# S7CAS-PLEIADES-CARTE-MERE_P07_ADC.net
KiCad netlist of a schematic drawn in Altium Designer
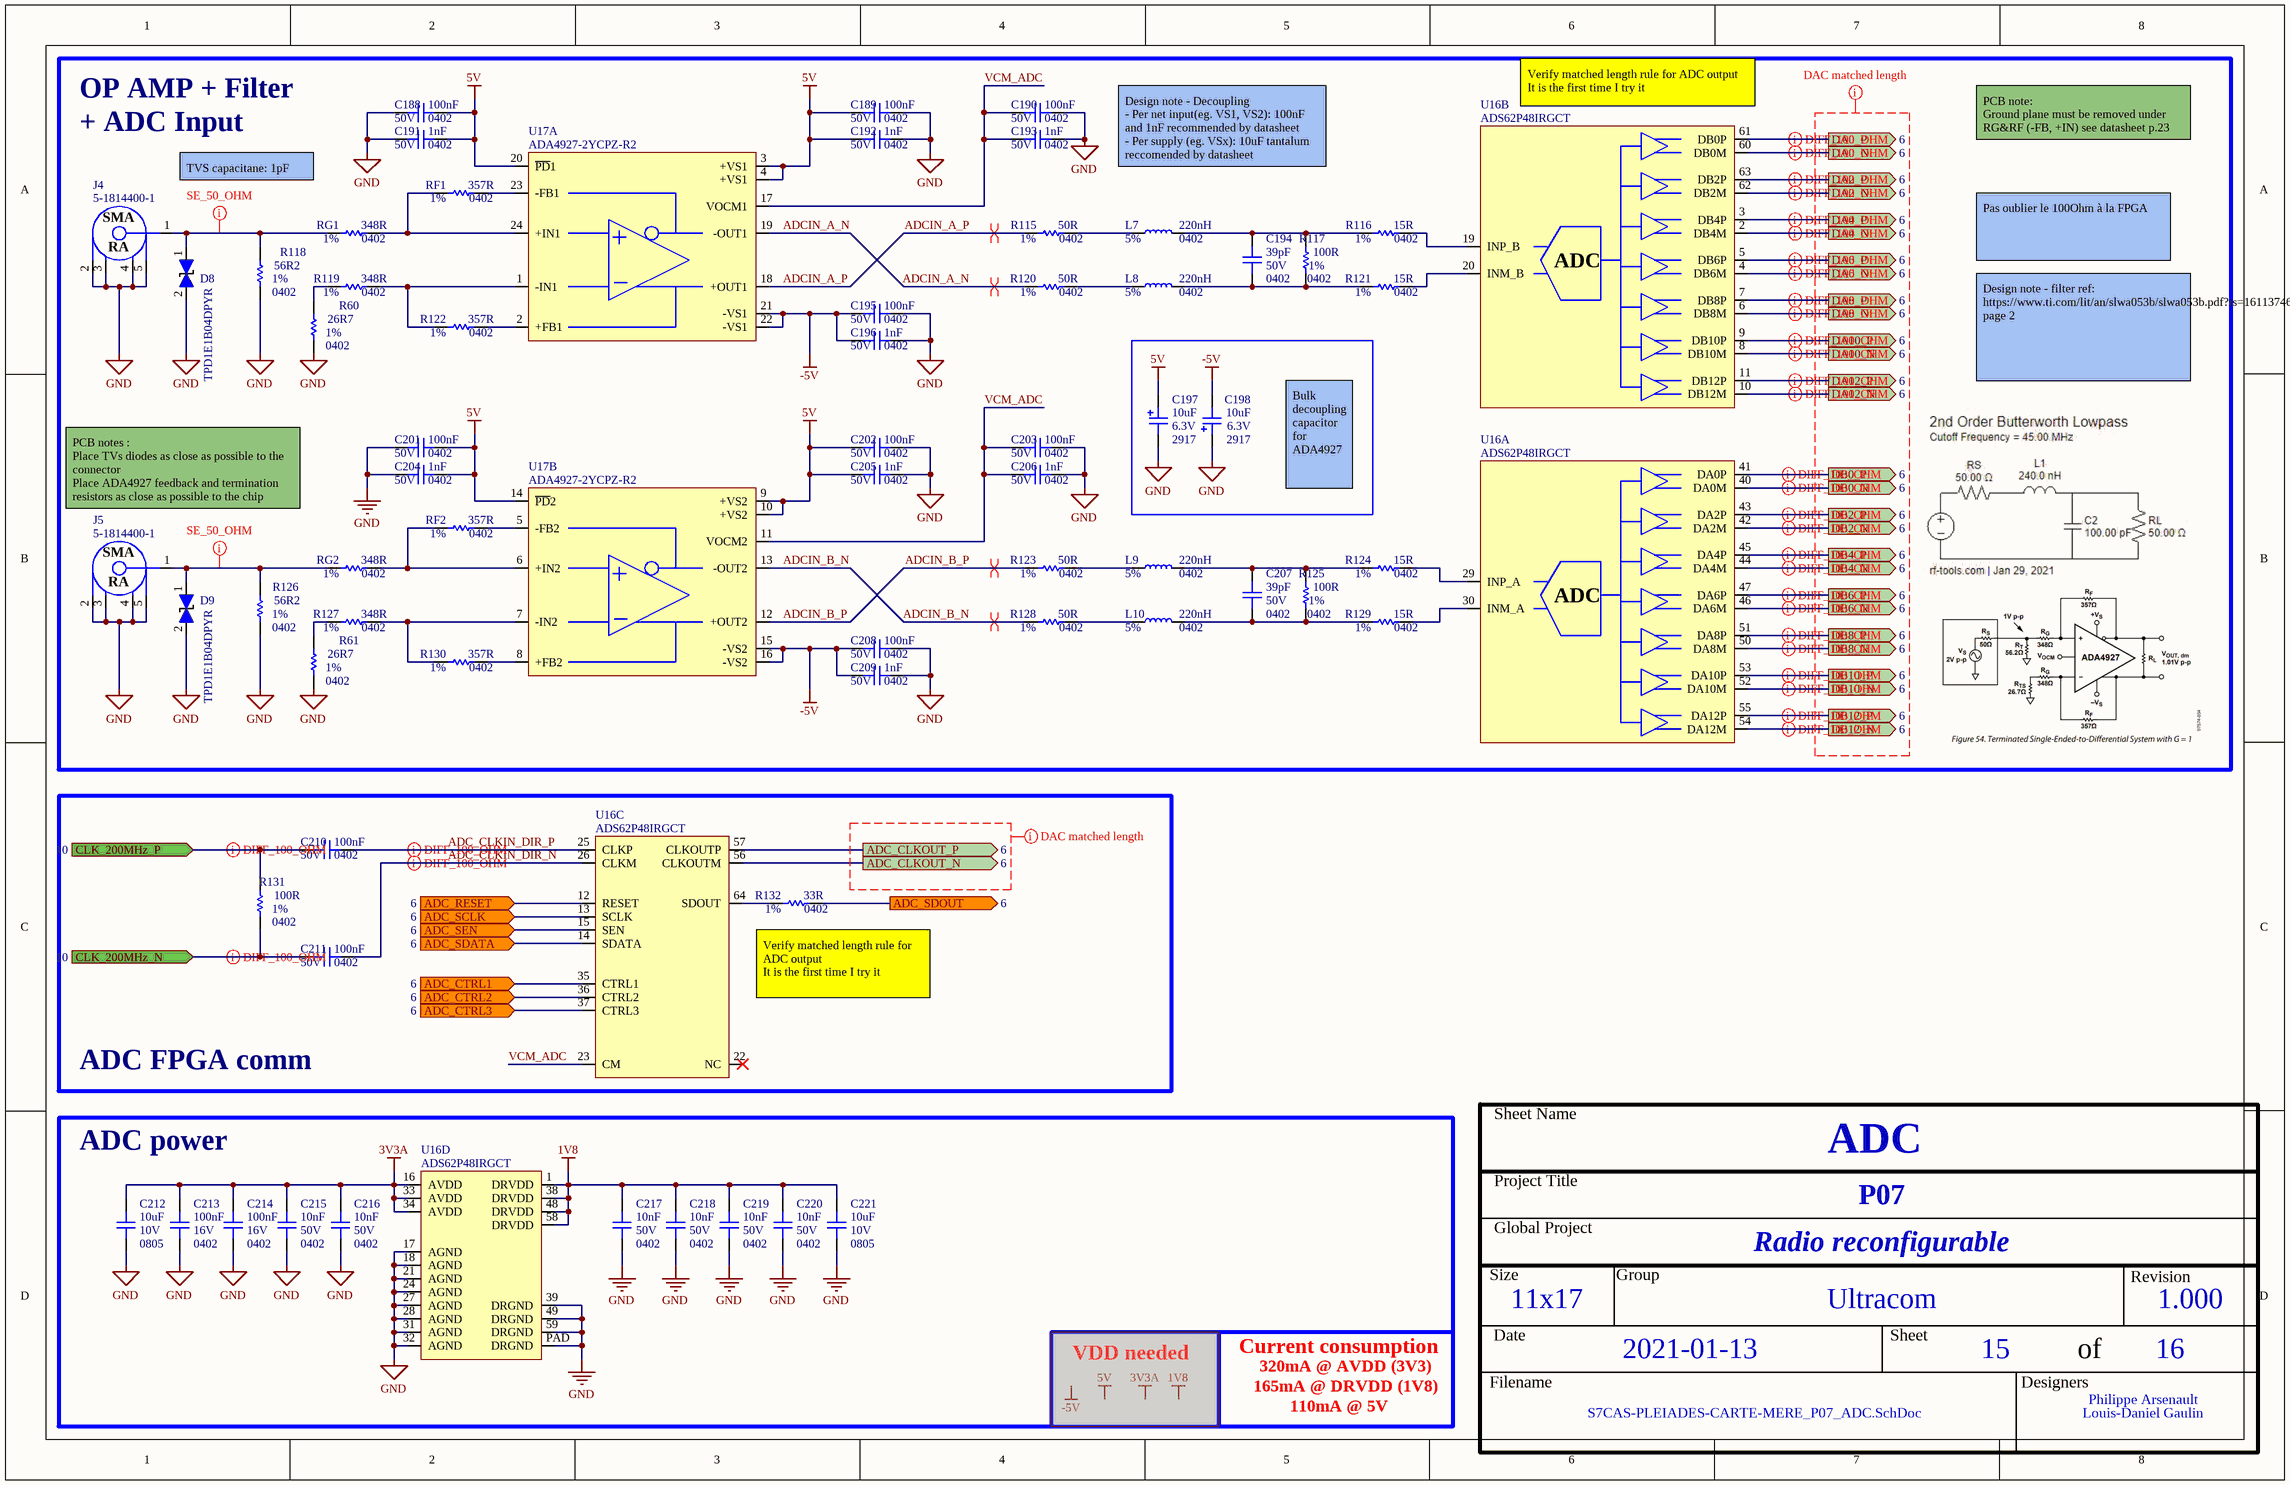
[diagram p0: S7CAS-PLEIADES-CARTE-MERE_P07_ADC.SchDoc]

(export (version "E")
  (design (tool "Eeschema 10.0.6"))
  (components
    (comp (ref "C188")
      (value "100nF")
      (footprint "CAP_0402")
      (description "CAP - 0402")
      (fields
        (field (name "VOLTAGE") "50V")
        (field (name "PACKAGE") "0402")
        (field (name "CREATEDBY") "Jonathan Bouchard")
      )
      (libsource (lib "S7CAS_LIB2021") (part "CAP - 0402"))
    )
    (comp (ref "C189")
      (value "100nF")
      (footprint "CAP_0402")
      (description "CAP - 0402")
      (fields
        (field (name "VOLTAGE") "50V")
        (field (name "PACKAGE") "0402")
        (field (name "CREATEDBY") "Jonathan Bouchard")
      )
      (libsource (lib "S7CAS_LIB2021") (part "CAP - 0402"))
    )
    (comp (ref "C190")
      (value "100nF")
      (footprint "CAP_0402")
      (description "CAP - 0402")
      (fields
        (field (name "VOLTAGE") "50V")
        (field (name "PACKAGE") "0402")
        (field (name "CREATEDBY") "Jonathan Bouchard")
      )
      (libsource (lib "S7CAS_LIB2021") (part "CAP - 0402"))
    )
    (comp (ref "C191")
      (value "1nF")
      (footprint "CAP_0402")
      (description "CAP - 0402")
      (fields
        (field (name "VOLTAGE") "50V")
        (field (name "PACKAGE") "0402")
        (field (name "CREATEDBY") "Jonathan Bouchard")
      )
      (libsource (lib "S7CAS_LIB2021") (part "CAP - 0402"))
    )
    (comp (ref "C192")
      (value "1nF")
      (footprint "CAP_0402")
      (description "CAP - 0402")
      (fields
        (field (name "VOLTAGE") "50V")
        (field (name "PACKAGE") "0402")
        (field (name "CREATEDBY") "Jonathan Bouchard")
      )
      (libsource (lib "S7CAS_LIB2021") (part "CAP - 0402"))
    )
    (comp (ref "C193")
      (value "1nF")
      (footprint "CAP_0402")
      (description "CAP - 0402")
      (fields
        (field (name "VOLTAGE") "50V")
        (field (name "PACKAGE") "0402")
        (field (name "CREATEDBY") "Jonathan Bouchard")
      )
      (libsource (lib "S7CAS_LIB2021") (part "CAP - 0402"))
    )
    (comp (ref "C194")
      (value "39pF")
      (footprint "CAP_0402")
      (description "CAP - 0402")
      (fields
        (field (name "VOLTAGE") "50V")
        (field (name "PACKAGE") "0402")
        (field (name "CREATEDBY") "Jonathan Bouchard")
      )
      (libsource (lib "S7CAS_LIB2021") (part "CAP - 0402"))
    )
    (comp (ref "C195")
      (value "100nF")
      (footprint "CAP_0402")
      (description "CAP - 0402")
      (fields
        (field (name "VOLTAGE") "50V")
        (field (name "PACKAGE") "0402")
        (field (name "CREATEDBY") "Jonathan Bouchard")
      )
      (libsource (lib "S7CAS_LIB2021") (part "CAP - 0402"))
    )
    (comp (ref "C196")
      (value "1nF")
      (footprint "CAP_0402")
      (description "CAP - 0402")
      (fields
        (field (name "VOLTAGE") "50V")
        (field (name "PACKAGE") "0402")
        (field (name "CREATEDBY") "Jonathan Bouchard")
      )
      (libsource (lib "S7CAS_LIB2021") (part "CAP - 0402"))
    )
    (comp (ref "C197")
      (value "10uF")
      (footprint "CAP_TAN_2917(D)")
      (description "CAP - TANTALUM - 2917")
      (fields
        (field (name "VOLTAGE") "6.3V")
        (field (name "PACKAGE") "2917")
        (field (name "Comment") "CAP - TANTALUM - CASE D")
        (field (name "CREATEDBY") "Jonathan Bouchard")
      )
      (libsource (lib "S7CAS_LIB2021") (part "CAP_TANT_2917(D)"))
    )
    (comp (ref "C198")
      (value "10uF")
      (footprint "CAP_TAN_2917(D)")
      (description "CAP - TANTALUM - 2917")
      (fields
        (field (name "VOLTAGE") "6.3V")
        (field (name "PACKAGE") "2917")
        (field (name "Comment") "CAP - TANTALUM - CASE D")
        (field (name "CREATEDBY") "Jonathan Bouchard")
      )
      (libsource (lib "S7CAS_LIB2021") (part "CAP_TANT_2917(D)"))
    )
    (comp (ref "C201")
      (value "100nF")
      (footprint "CAP_0402")
      (description "CAP - 0402")
      (fields
        (field (name "VOLTAGE") "50V")
        (field (name "PACKAGE") "0402")
        (field (name "CREATEDBY") "Jonathan Bouchard")
      )
      (libsource (lib "S7CAS_LIB2021") (part "CAP - 0402"))
    )
    (comp (ref "C202")
      (value "100nF")
      (footprint "CAP_0402")
      (description "CAP - 0402")
      (fields
        (field (name "VOLTAGE") "50V")
        (field (name "PACKAGE") "0402")
        (field (name "CREATEDBY") "Jonathan Bouchard")
      )
      (libsource (lib "S7CAS_LIB2021") (part "CAP - 0402"))
    )
    (comp (ref "C203")
      (value "100nF")
      (footprint "CAP_0402")
      (description "CAP - 0402")
      (fields
        (field (name "VOLTAGE") "50V")
        (field (name "PACKAGE") "0402")
        (field (name "CREATEDBY") "Jonathan Bouchard")
      )
      (libsource (lib "S7CAS_LIB2021") (part "CAP - 0402"))
    )
    (comp (ref "C204")
      (value "1nF")
      (footprint "CAP_0402")
      (description "CAP - 0402")
      (fields
        (field (name "VOLTAGE") "50V")
        (field (name "PACKAGE") "0402")
        (field (name "CREATEDBY") "Jonathan Bouchard")
      )
      (libsource (lib "S7CAS_LIB2021") (part "CAP - 0402"))
    )
    (comp (ref "C205")
      (value "1nF")
      (footprint "CAP_0402")
      (description "CAP - 0402")
      (fields
        (field (name "VOLTAGE") "50V")
        (field (name "PACKAGE") "0402")
        (field (name "CREATEDBY") "Jonathan Bouchard")
      )
      (libsource (lib "S7CAS_LIB2021") (part "CAP - 0402"))
    )
    (comp (ref "C206")
      (value "1nF")
      (footprint "CAP_0402")
      (description "CAP - 0402")
      (fields
        (field (name "VOLTAGE") "50V")
        (field (name "PACKAGE") "0402")
        (field (name "CREATEDBY") "Jonathan Bouchard")
      )
      (libsource (lib "S7CAS_LIB2021") (part "CAP - 0402"))
    )
    (comp (ref "C207")
      (value "39pF")
      (footprint "CAP_0402")
      (description "CAP - 0402")
      (fields
        (field (name "VOLTAGE") "50V")
        (field (name "PACKAGE") "0402")
        (field (name "CREATEDBY") "Jonathan Bouchard")
      )
      (libsource (lib "S7CAS_LIB2021") (part "CAP - 0402"))
    )
    (comp (ref "C208")
      (value "100nF")
      (footprint "CAP_0402")
      (description "CAP - 0402")
      (fields
        (field (name "VOLTAGE") "50V")
        (field (name "PACKAGE") "0402")
        (field (name "CREATEDBY") "Jonathan Bouchard")
      )
      (libsource (lib "S7CAS_LIB2021") (part "CAP - 0402"))
    )
    (comp (ref "C209")
      (value "1nF")
      (footprint "CAP_0402")
      (description "CAP - 0402")
      (fields
        (field (name "VOLTAGE") "50V")
        (field (name "PACKAGE") "0402")
        (field (name "CREATEDBY") "Jonathan Bouchard")
      )
      (libsource (lib "S7CAS_LIB2021") (part "CAP - 0402"))
    )
    (comp (ref "C210")
      (value "100nF")
      (footprint "CAP_0402")
      (description "CAP - 0402")
      (fields
        (field (name "VOLTAGE") "50V")
        (field (name "PACKAGE") "0402")
        (field (name "CREATEDBY") "Jonathan Bouchard")
      )
      (libsource (lib "S7CAS_LIB2021") (part "CAP - 0402"))
    )
    (comp (ref "C211")
      (value "100nF")
      (footprint "CAP_0402")
      (description "CAP - 0402")
      (fields
        (field (name "VOLTAGE") "50V")
        (field (name "PACKAGE") "0402")
        (field (name "CREATEDBY") "Jonathan Bouchard")
      )
      (libsource (lib "S7CAS_LIB2021") (part "CAP - 0402"))
    )
    (comp (ref "C212")
      (value "10uF")
      (footprint "CAP_0805")
      (description "CAP - 0805")
      (fields
        (field (name "MFG") "CL21B106KPQNNNE")
        (field (name "VOLTAGE") "10V")
        (field (name "PACKAGE") "0805")
        (field (name "CREATEDBY") "Jonathan Bouchard")
      )
      (libsource (lib "S7CAS_LIB2021") (part "CAP - 0805"))
    )
    (comp (ref "C213")
      (value "100nF")
      (footprint "CAP_0402")
      (description "CAP - 0402")
      (fields
        (field (name "MFG PART NUMBER") "CL05B104KO5NNNC")
        (field (name "VOLTAGE") "16V")
        (field (name "PACKAGE") "0402")
        (field (name "CREATEDBY") "Jonathan Bouchard")
      )
      (libsource (lib "S7CAS_LIB2021") (part "CAP - 0402"))
    )
    (comp (ref "C214")
      (value "100nF")
      (footprint "CAP_0402")
      (description "CAP - 0402")
      (fields
        (field (name "MFG PART NUMBER") "CL05B104KO5NNNC")
        (field (name "VOLTAGE") "16V")
        (field (name "PACKAGE") "0402")
        (field (name "CREATEDBY") "Jonathan Bouchard")
      )
      (libsource (lib "S7CAS_LIB2021") (part "CAP - 0402"))
    )
    (comp (ref "C215")
      (value "10nF")
      (footprint "CAP_0402")
      (description "CAP - 0402")
      (fields
        (field (name "MFG PART NUMBER") "CL05B103KB5NNNC")
        (field (name "VOLTAGE") "50V")
        (field (name "PACKAGE") "0402")
        (field (name "CREATEDBY") "Jonathan Bouchard")
      )
      (libsource (lib "S7CAS_LIB2021") (part "CAP - 0402"))
    )
    (comp (ref "C216")
      (value "10nF")
      (footprint "CAP_0402")
      (description "CAP - 0402")
      (fields
        (field (name "MFG PART NUMBER") "CL05B103KB5NNNC")
        (field (name "VOLTAGE") "50V")
        (field (name "PACKAGE") "0402")
        (field (name "CREATEDBY") "Jonathan Bouchard")
      )
      (libsource (lib "S7CAS_LIB2021") (part "CAP - 0402"))
    )
    (comp (ref "C217")
      (value "10nF")
      (footprint "CAP_0402")
      (description "CAP - 0402")
      (fields
        (field (name "MFG PART NUMBER") "CL05B103KB5NNNC")
        (field (name "VOLTAGE") "50V")
        (field (name "PACKAGE") "0402")
        (field (name "CREATEDBY") "Jonathan Bouchard")
      )
      (libsource (lib "S7CAS_LIB2021") (part "CAP - 0402"))
    )
    (comp (ref "C218")
      (value "10nF")
      (footprint "CAP_0402")
      (description "CAP - 0402")
      (fields
        (field (name "MFG PART NUMBER") "CL05B103KB5NNNC")
        (field (name "VOLTAGE") "50V")
        (field (name "PACKAGE") "0402")
        (field (name "CREATEDBY") "Jonathan Bouchard")
      )
      (libsource (lib "S7CAS_LIB2021") (part "CAP - 0402"))
    )
    (comp (ref "C219")
      (value "10nF")
      (footprint "CAP_0402")
      (description "CAP - 0402")
      (fields
        (field (name "MFG PART NUMBER") "CL05B103KB5NNNC")
        (field (name "VOLTAGE") "50V")
        (field (name "PACKAGE") "0402")
        (field (name "CREATEDBY") "Jonathan Bouchard")
      )
      (libsource (lib "S7CAS_LIB2021") (part "CAP - 0402"))
    )
    (comp (ref "C220")
      (value "10nF")
      (footprint "CAP_0402")
      (description "CAP - 0402")
      (fields
        (field (name "MFG PART NUMBER") "CL05B103KB5NNNC")
        (field (name "VOLTAGE") "50V")
        (field (name "PACKAGE") "0402")
        (field (name "CREATEDBY") "Jonathan Bouchard")
      )
      (libsource (lib "S7CAS_LIB2021") (part "CAP - 0402"))
    )
    (comp (ref "C221")
      (value "10uF")
      (footprint "CAP_0805")
      (description "CAP - 0805")
      (fields
        (field (name "MFG") "CL21B106KPQNNNE")
        (field (name "VOLTAGE") "10V")
        (field (name "PACKAGE") "0805")
        (field (name "CREATEDBY") "Jonathan Bouchard")
      )
      (libsource (lib "S7CAS_LIB2021") (part "CAP - 0805"))
    )
    (comp (ref "D8")
      (value "TPD1E1B04DPYR")
      (footprint "TVS_DATA_TPD1E1B04DPYR")
      (description "TVS - TVS DIODE 3.6V 8.5V - 0402")
      (fields
        (field (name "CREATEDBY/DATE") "Keven Deslandes - 2018/10/19")
        (field (name "VERIFIEDBY") "Caroline Paulin - 28 janv 2019")
      )
      (libsource (lib "S7CAS_LIB2021") (part "TVS_DATA_TPD1E1B04DPYR"))
    )
    (comp (ref "D9")
      (value "TPD1E1B04DPYR")
      (footprint "TVS_DATA_TPD1E1B04DPYR")
      (description "TVS - TVS DIODE 3.6V 8.5V - 0402")
      (fields
        (field (name "CREATEDBY/DATE") "Keven Deslandes - 2018/10/19")
        (field (name "VERIFIEDBY") "Caroline Paulin - 28 janv 2019")
      )
      (libsource (lib "S7CAS_LIB2021") (part "TVS_DATA_TPD1E1B04DPYR"))
    )
    (comp (ref "J4")
      (value "5-1814400-1")
      (footprint "CONN_SMA_5-1814400-1")
      (description "CONN -  SMA JACK R/A 50 OHM - TH")
      (fields
        (field (name "MFG") "TE Connectivity AMP Connectors")
        (field (name "CREATEDBY") "Jonathan Bouchard")
      )
      (libsource (lib "S7CAS_LIB2021") (part "CONN_SMA_5-1814400-1"))
    )
    (comp (ref "J5")
      (value "5-1814400-1")
      (footprint "CONN_SMA_5-1814400-1")
      (description "CONN -  SMA JACK R/A 50 OHM - TH")
      (fields
        (field (name "MFG") "TE Connectivity AMP Connectors")
        (field (name "CREATEDBY") "Jonathan Bouchard")
      )
      (libsource (lib "S7CAS_LIB2021") (part "CONN_SMA_5-1814400-1"))
    )
    (comp (ref "L7")
      (value "220nH")
      (footprint "IND_0402")
      (description "IND_0402")
      (fields
        (field (name "PRECISION") "5%")
        (field (name "PACKAGE") "0402")
        (field (name "CREATEDBY") "Jonathan Bouchard")
      )
      (libsource (lib "S7CAS_P07") (part "IND_0402"))
    )
    (comp (ref "L8")
      (value "220nH")
      (footprint "IND_0402")
      (description "IND_0402")
      (fields
        (field (name "PRECISION") "5%")
        (field (name "PACKAGE") "0402")
        (field (name "CREATEDBY") "Jonathan Bouchard")
      )
      (libsource (lib "S7CAS_P07") (part "IND_0402"))
    )
    (comp (ref "L9")
      (value "220nH")
      (footprint "IND_0402")
      (description "IND_0402")
      (fields
        (field (name "PRECISION") "5%")
        (field (name "PACKAGE") "0402")
        (field (name "CREATEDBY") "Jonathan Bouchard")
      )
      (libsource (lib "S7CAS_P07") (part "IND_0402"))
    )
    (comp (ref "L10")
      (value "220nH")
      (footprint "IND_0402")
      (description "IND_0402")
      (fields
        (field (name "PRECISION") "5%")
        (field (name "PACKAGE") "0402")
        (field (name "CREATEDBY") "Jonathan Bouchard")
      )
      (libsource (lib "S7CAS_P07") (part "IND_0402"))
    )
    (comp (ref "R60")
      (value "26R7")
      (footprint "RES_0402")
      (description "RES - 0402")
      (fields
        (field (name "VOLTAGE") "50V")
        (field (name "POWER") "1/16W")
        (field (name "PACKAGE") "0402")
        (field (name "PRECISION") "1%")
        (field (name "CREATEDBY") "Jonathan Bouchard")
      )
      (libsource (lib "S7CAS_LIB2021") (part "RES - 0402"))
    )
    (comp (ref "R61")
      (value "26R7")
      (footprint "RES_0402")
      (description "RES - 0402")
      (fields
        (field (name "VOLTAGE") "50V")
        (field (name "POWER") "1/16W")
        (field (name "PACKAGE") "0402")
        (field (name "PRECISION") "1%")
        (field (name "CREATEDBY") "Jonathan Bouchard")
      )
      (libsource (lib "S7CAS_LIB2021") (part "RES - 0402"))
    )
    (comp (ref "R115")
      (value "50R")
      (footprint "RES_0402")
      (description "RES - 0402")
      (fields
        (field (name "VOLTAGE") "50V")
        (field (name "POWER") "1/16W")
        (field (name "PACKAGE") "0402")
        (field (name "PRECISION") "1%")
        (field (name "CREATEDBY") "Jonathan Bouchard")
      )
      (libsource (lib "S7CAS_LIB2021") (part "RES - 0402"))
    )
    (comp (ref "R116")
      (value "15R")
      (footprint "RES_0402")
      (description "RES - 0402")
      (fields
        (field (name "VOLTAGE") "50V")
        (field (name "POWER") "1/16W")
        (field (name "PACKAGE") "0402")
        (field (name "PRECISION") "1%")
        (field (name "CREATEDBY") "Jonathan Bouchard")
      )
      (libsource (lib "S7CAS_LIB2021") (part "RES - 0402"))
    )
    (comp (ref "R117")
      (value "100R")
      (footprint "RES_0402")
      (description "RES - 0402")
      (fields
        (field (name "VOLTAGE") "50V")
        (field (name "POWER") "1/16W")
        (field (name "PACKAGE") "0402")
        (field (name "PRECISION") "1%")
        (field (name "CREATEDBY") "Jonathan Bouchard")
      )
      (libsource (lib "S7CAS_LIB2021") (part "RES - 0402"))
    )
    (comp (ref "R118")
      (value "56R2")
      (footprint "RES_0402")
      (description "RES - 0402")
      (fields
        (field (name "VOLTAGE") "50V")
        (field (name "POWER") "1/16W")
        (field (name "PACKAGE") "0402")
        (field (name "PRECISION") "1%")
        (field (name "CREATEDBY") "Jonathan Bouchard")
      )
      (libsource (lib "S7CAS_LIB2021") (part "RES - 0402"))
    )
    (comp (ref "R119")
      (value "348R")
      (footprint "RES_0402")
      (description "RES - 0402")
      (fields
        (field (name "VOLTAGE") "50V")
        (field (name "POWER") "1/16W")
        (field (name "PACKAGE") "0402")
        (field (name "PRECISION") "1%")
        (field (name "CREATEDBY") "Jonathan Bouchard")
      )
      (libsource (lib "S7CAS_LIB2021") (part "RES - 0402"))
    )
    (comp (ref "R120")
      (value "50R")
      (footprint "RES_0402")
      (description "RES - 0402")
      (fields
        (field (name "VOLTAGE") "50V")
        (field (name "POWER") "1/16W")
        (field (name "PACKAGE") "0402")
        (field (name "PRECISION") "1%")
        (field (name "CREATEDBY") "Jonathan Bouchard")
      )
      (libsource (lib "S7CAS_LIB2021") (part "RES - 0402"))
    )
    (comp (ref "R121")
      (value "15R")
      (footprint "RES_0402")
      (description "RES - 0402")
      (fields
        (field (name "VOLTAGE") "50V")
        (field (name "POWER") "1/16W")
        (field (name "PACKAGE") "0402")
        (field (name "PRECISION") "1%")
        (field (name "CREATEDBY") "Jonathan Bouchard")
      )
      (libsource (lib "S7CAS_LIB2021") (part "RES - 0402"))
    )
    (comp (ref "R122")
      (value "357R")
      (footprint "RES_0402")
      (description "RES - 0402")
      (fields
        (field (name "VOLTAGE") "50V")
        (field (name "POWER") "1/16W")
        (field (name "PACKAGE") "0402")
        (field (name "PRECISION") "1%")
        (field (name "CREATEDBY") "Jonathan Bouchard")
      )
      (libsource (lib "S7CAS_LIB2021") (part "RES - 0402"))
    )
    (comp (ref "R123")
      (value "50R")
      (footprint "RES_0402")
      (description "RES - 0402")
      (fields
        (field (name "VOLTAGE") "50V")
        (field (name "POWER") "1/16W")
        (field (name "PACKAGE") "0402")
        (field (name "PRECISION") "1%")
        (field (name "CREATEDBY") "Jonathan Bouchard")
      )
      (libsource (lib "S7CAS_LIB2021") (part "RES - 0402"))
    )
    (comp (ref "R124")
      (value "15R")
      (footprint "RES_0402")
      (description "RES - 0402")
      (fields
        (field (name "VOLTAGE") "50V")
        (field (name "POWER") "1/16W")
        (field (name "PACKAGE") "0402")
        (field (name "PRECISION") "1%")
        (field (name "CREATEDBY") "Jonathan Bouchard")
      )
      (libsource (lib "S7CAS_LIB2021") (part "RES - 0402"))
    )
    (comp (ref "R125")
      (value "100R")
      (footprint "RES_0402")
      (description "RES - 0402")
      (fields
        (field (name "VOLTAGE") "50V")
        (field (name "POWER") "1/16W")
        (field (name "PACKAGE") "0402")
        (field (name "PRECISION") "1%")
        (field (name "CREATEDBY") "Jonathan Bouchard")
      )
      (libsource (lib "S7CAS_LIB2021") (part "RES - 0402"))
    )
    (comp (ref "R126")
      (value "56R2")
      (footprint "RES_0402")
      (description "RES - 0402")
      (fields
        (field (name "VOLTAGE") "50V")
        (field (name "POWER") "1/16W")
        (field (name "PACKAGE") "0402")
        (field (name "PRECISION") "1%")
        (field (name "CREATEDBY") "Jonathan Bouchard")
      )
      (libsource (lib "S7CAS_LIB2021") (part "RES - 0402"))
    )
    (comp (ref "R127")
      (value "348R")
      (footprint "RES_0402")
      (description "RES - 0402")
      (fields
        (field (name "VOLTAGE") "50V")
        (field (name "POWER") "1/16W")
        (field (name "PACKAGE") "0402")
        (field (name "PRECISION") "1%")
        (field (name "CREATEDBY") "Jonathan Bouchard")
      )
      (libsource (lib "S7CAS_LIB2021") (part "RES - 0402"))
    )
    (comp (ref "R128")
      (value "50R")
      (footprint "RES_0402")
      (description "RES - 0402")
      (fields
        (field (name "VOLTAGE") "50V")
        (field (name "POWER") "1/16W")
        (field (name "PACKAGE") "0402")
        (field (name "PRECISION") "1%")
        (field (name "CREATEDBY") "Jonathan Bouchard")
      )
      (libsource (lib "S7CAS_LIB2021") (part "RES - 0402"))
    )
    (comp (ref "R129")
      (value "15R")
      (footprint "RES_0402")
      (description "RES - 0402")
      (fields
        (field (name "VOLTAGE") "50V")
        (field (name "POWER") "1/16W")
        (field (name "PACKAGE") "0402")
        (field (name "PRECISION") "1%")
        (field (name "CREATEDBY") "Jonathan Bouchard")
      )
      (libsource (lib "S7CAS_LIB2021") (part "RES - 0402"))
    )
    (comp (ref "R130")
      (value "357R")
      (footprint "RES_0402")
      (description "RES - 0402")
      (fields
        (field (name "VOLTAGE") "50V")
        (field (name "POWER") "1/16W")
        (field (name "PACKAGE") "0402")
        (field (name "PRECISION") "1%")
        (field (name "CREATEDBY") "Jonathan Bouchard")
      )
      (libsource (lib "S7CAS_LIB2021") (part "RES - 0402"))
    )
    (comp (ref "R131")
      (value "100R")
      (footprint "RES_0402")
      (description "RES - 0402")
      (fields
        (field (name "VOLTAGE") "50V")
        (field (name "POWER") "1/16W")
        (field (name "PACKAGE") "0402")
        (field (name "PRECISION") "1%")
        (field (name "CREATEDBY") "Jonathan Bouchard")
      )
      (libsource (lib "S7CAS_LIB2021") (part "RES - 0402"))
    )
    (comp (ref "R132")
      (value "33R")
      (footprint "RES_0402")
      (description "RES - 0402")
      (fields
        (field (name "VOLTAGE") "50V")
        (field (name "POWER") "1/16W")
        (field (name "PACKAGE") "0402")
        (field (name "PRECISION") "1%")
        (field (name "CREATEDBY") "Jonathan Bouchard")
      )
      (libsource (lib "S7CAS_LIB2021") (part "RES - 0402"))
    )
    (comp (ref "RF1")
      (value "357R")
      (footprint "RES_0402")
      (description "RES - 0402")
      (fields
        (field (name "VOLTAGE") "50V")
        (field (name "POWER") "1/16W")
        (field (name "PACKAGE") "0402")
        (field (name "PRECISION") "1%")
        (field (name "CREATEDBY") "Jonathan Bouchard")
      )
      (libsource (lib "S7CAS_LIB2021") (part "RES - 0402"))
    )
    (comp (ref "RF2")
      (value "357R")
      (footprint "RES_0402")
      (description "RES - 0402")
      (fields
        (field (name "VOLTAGE") "50V")
        (field (name "POWER") "1/16W")
        (field (name "PACKAGE") "0402")
        (field (name "PRECISION") "1%")
        (field (name "CREATEDBY") "Jonathan Bouchard")
      )
      (libsource (lib "S7CAS_LIB2021") (part "RES - 0402"))
    )
    (comp (ref "RG1")
      (value "348R")
      (footprint "RES_0402")
      (description "RES - 0402")
      (fields
        (field (name "VOLTAGE") "50V")
        (field (name "POWER") "1/16W")
        (field (name "PACKAGE") "0402")
        (field (name "PRECISION") "1%")
        (field (name "CREATEDBY") "Jonathan Bouchard")
      )
      (libsource (lib "S7CAS_LIB2021") (part "RES - 0402"))
    )
    (comp (ref "RG2")
      (value "348R")
      (footprint "RES_0402")
      (description "RES - 0402")
      (fields
        (field (name "VOLTAGE") "50V")
        (field (name "POWER") "1/16W")
        (field (name "PACKAGE") "0402")
        (field (name "PRECISION") "1%")
        (field (name "CREATEDBY") "Jonathan Bouchard")
      )
      (libsource (lib "S7CAS_LIB2021") (part "RES - 0402"))
    )
    (comp (ref "U16")
      (value "ADS62P48IRGCT")
      (footprint "ADC_ADS62P48IRGCT")
      (description "ADC - 14 BIT 210MSPS SUAL - VQFN-64")
      (fields
        (field (name "VOLTAGE") "3.15 V ~ 3.6 V / 1.7 V ~ 1.9 V")
        (field (name "MFG") "Texas Instruments")
        (field (name "CREATEDBY") "Jonathan Bouchard")
      )
      (libsource (lib "S7CAS_LIB2021") (part "ADC_ADS62P48IRGCT"))
    )
    (comp (ref "U17")
      (value "ADA4927-2YCPZ-R2")
      (footprint "OPAMP_ADA4927-2YCPZ-R2")
      (description "OPAMP - CFA 2.3GHZ - QFN-24")
      (fields
        (field (name "VOLTAGE") "4.5 V ~ 11 V, ±2.25 V ~ 5.5 V")
        (field (name "MFG") "Analog Devices")
        (field (name "CREATEDBY") "Jonathan Bouchard")
      )
      (libsource (lib "S7CAS_LIB2021") (part "OPAMP_ADA4927-2YCPZ-R2"))
    )
  )
  (nets
    (net (code "1") (name "-5V") (class "Default")
      (node (ref "C195") (pin "2") (pinfunction "2_2") (pintype "passive"))
      (node (ref "C196") (pin "2") (pinfunction "2_2") (pintype "passive"))
      (node (ref "C198") (pin "2") (pinfunction "2_2") (pintype "passive"))
      (node (ref "C208") (pin "2") (pinfunction "2_2") (pintype "passive"))
      (node (ref "C209") (pin "2") (pinfunction "2_2") (pintype "passive"))
      (node (ref "U17") (pin "15") (pinfunction "-VS2_15") (pintype "passive"))
      (node (ref "U17") (pin "16") (pinfunction "-VS2_16") (pintype "passive"))
      (node (ref "U17") (pin "21") (pinfunction "-VS1_21") (pintype "passive"))
      (node (ref "U17") (pin "22") (pinfunction "-VS1_22") (pintype "passive"))
    )
    (net (code "2") (name "/ADCIN_A_N") (class "Default")
      (node (ref "R120") (pin "2") (pinfunction "2_2") (pintype "passive"))
      (node (ref "U17") (pin "19") (pinfunction "-OUT1_19") (pintype "passive"))
    )
    (net (code "3") (name "/ADCIN_A_P") (class "Default")
      (node (ref "R115") (pin "2") (pinfunction "2_2") (pintype "passive"))
      (node (ref "U17") (pin "18") (pinfunction "+OUT1_18") (pintype "passive"))
    )
    (net (code "4") (name "/ADCIN_B_N") (class "Default")
      (node (ref "R128") (pin "2") (pinfunction "2_2") (pintype "passive"))
      (node (ref "U17") (pin "13") (pinfunction "-OUT2_13") (pintype "passive"))
    )
    (net (code "5") (name "/ADCIN_B_P") (class "Default")
      (node (ref "R123") (pin "2") (pinfunction "2_2") (pintype "passive"))
      (node (ref "U17") (pin "12") (pinfunction "+OUT2_12") (pintype "passive"))
    )
    (net (code "6") (name "/ADC_CLKIN_DIR_N") (class "Default")
      (node (ref "C211") (pin "1") (pinfunction "1_1") (pintype "passive"))
      (node (ref "U16") (pin "26") (pinfunction "CLKM_26") (pintype "passive"))
    )
    (net (code "7") (name "/ADC_CLKIN_DIR_P") (class "Default")
      (node (ref "C210") (pin "1") (pinfunction "1_1") (pintype "passive"))
      (node (ref "U16") (pin "25") (pinfunction "CLKP_25") (pintype "passive"))
    )
    (net (code "8") (name "/ADC_CLKOUT_N") (class "Default")
      (node (ref "U16") (pin "56") (pinfunction "CLKOUTM_56") (pintype "passive"))
    )
    (net (code "9") (name "/ADC_CLKOUT_P") (class "Default")
      (node (ref "U16") (pin "57") (pinfunction "CLKOUTP_57") (pintype "passive"))
    )
    (net (code "10") (name "/ADC_CTRL1") (class "Default")
      (node (ref "U16") (pin "35") (pinfunction "CTRL1_35") (pintype "passive"))
    )
    (net (code "11") (name "/ADC_CTRL2") (class "Default")
      (node (ref "U16") (pin "36") (pinfunction "CTRL2_36") (pintype "passive"))
    )
    (net (code "12") (name "/ADC_CTRL3") (class "Default")
      (node (ref "U16") (pin "37") (pinfunction "CTRL3_37") (pintype "passive"))
    )
    (net (code "13") (name "/ADC_RESET") (class "Default")
      (node (ref "U16") (pin "12") (pinfunction "RESET_12") (pintype "passive"))
    )
    (net (code "14") (name "/ADC_SCLK") (class "Default")
      (node (ref "U16") (pin "13") (pinfunction "SCLK_13") (pintype "passive"))
    )
    (net (code "15") (name "/ADC_SDATA") (class "Default")
      (node (ref "U16") (pin "14") (pinfunction "SDATA_14") (pintype "passive"))
    )
    (net (code "16") (name "/ADC_SDOUT") (class "Default")
      (node (ref "R132") (pin "1") (pinfunction "1_1") (pintype "passive"))
    )
    (net (code "17") (name "/ADC_SEN") (class "Default")
      (node (ref "U16") (pin "15") (pinfunction "SEN_15") (pintype "passive"))
    )
    (net (code "18") (name "/CLK_200MHz_N") (class "Default")
      (node (ref "C211") (pin "2") (pinfunction "2_2") (pintype "passive"))
      (node (ref "R131") (pin "1") (pinfunction "1_1") (pintype "passive"))
    )
    (net (code "19") (name "/CLK_200MHz_P") (class "Default")
      (node (ref "C210") (pin "2") (pinfunction "2_2") (pintype "passive"))
      (node (ref "R131") (pin "2") (pinfunction "2_2") (pintype "passive"))
    )
    (net (code "20") (name "/DA0_N") (class "Default")
      (node (ref "U16") (pin "60") (pinfunction "DB0M_60") (pintype "passive"))
    )
    (net (code "21") (name "/DA0_P") (class "Default")
      (node (ref "U16") (pin "61") (pinfunction "DB0P_61") (pintype "passive"))
    )
    (net (code "22") (name "/DA2_N") (class "Default")
      (node (ref "U16") (pin "62") (pinfunction "DB2M_62") (pintype "passive"))
    )
    (net (code "23") (name "/DA2_P") (class "Default")
      (node (ref "U16") (pin "63") (pinfunction "DB2P_63") (pintype "passive"))
    )
    (net (code "24") (name "/DA4_N") (class "Default")
      (node (ref "U16") (pin "2") (pinfunction "DB4M_2") (pintype "passive"))
    )
    (net (code "25") (name "/DA4_P") (class "Default")
      (node (ref "U16") (pin "3") (pinfunction "DB4P_3") (pintype "passive"))
    )
    (net (code "26") (name "/DA6_N") (class "Default")
      (node (ref "U16") (pin "4") (pinfunction "DB6M_4") (pintype "passive"))
    )
    (net (code "27") (name "/DA6_P") (class "Default")
      (node (ref "U16") (pin "5") (pinfunction "DB6P_5") (pintype "passive"))
    )
    (net (code "28") (name "/DA8_N") (class "Default")
      (node (ref "U16") (pin "6") (pinfunction "DB8M_6") (pintype "passive"))
    )
    (net (code "29") (name "/DA8_P") (class "Default")
      (node (ref "U16") (pin "7") (pinfunction "DB8P_7") (pintype "passive"))
    )
    (net (code "30") (name "/DA10_N") (class "Default")
      (node (ref "U16") (pin "8") (pinfunction "DB10M_8") (pintype "passive"))
    )
    (net (code "31") (name "/DA10_P") (class "Default")
      (node (ref "U16") (pin "9") (pinfunction "DB10P_9") (pintype "passive"))
    )
    (net (code "32") (name "/DA12_N") (class "Default")
      (node (ref "U16") (pin "10") (pinfunction "DB12M_10") (pintype "passive"))
    )
    (net (code "33") (name "/DA12_P") (class "Default")
      (node (ref "U16") (pin "11") (pinfunction "DB12P_11") (pintype "passive"))
    )
    (net (code "34") (name "/DB0_N") (class "Default")
      (node (ref "U16") (pin "40") (pinfunction "DA0M_40") (pintype "passive"))
    )
    (net (code "35") (name "/DB0_P") (class "Default")
      (node (ref "U16") (pin "41") (pinfunction "DA0P_41") (pintype "passive"))
    )
    (net (code "36") (name "/DB2_N") (class "Default")
      (node (ref "U16") (pin "42") (pinfunction "DA2M_42") (pintype "passive"))
    )
    (net (code "37") (name "/DB2_P") (class "Default")
      (node (ref "U16") (pin "43") (pinfunction "DA2P_43") (pintype "passive"))
    )
    (net (code "38") (name "/DB4_N") (class "Default")
      (node (ref "U16") (pin "44") (pinfunction "DA4M_44") (pintype "passive"))
    )
    (net (code "39") (name "/DB4_P") (class "Default")
      (node (ref "U16") (pin "45") (pinfunction "DA4P_45") (pintype "passive"))
    )
    (net (code "40") (name "/DB6_N") (class "Default")
      (node (ref "U16") (pin "46") (pinfunction "DA6M_46") (pintype "passive"))
    )
    (net (code "41") (name "/DB6_P") (class "Default")
      (node (ref "U16") (pin "47") (pinfunction "DA6P_47") (pintype "passive"))
    )
    (net (code "42") (name "/DB8_N") (class "Default")
      (node (ref "U16") (pin "50") (pinfunction "DA8M_50") (pintype "passive"))
    )
    (net (code "43") (name "/DB8_P") (class "Default")
      (node (ref "U16") (pin "51") (pinfunction "DA8P_51") (pintype "passive"))
    )
    (net (code "44") (name "/DB10_N") (class "Default")
      (node (ref "U16") (pin "52") (pinfunction "DA10M_52") (pintype "passive"))
    )
    (net (code "45") (name "/DB10_P") (class "Default")
      (node (ref "U16") (pin "53") (pinfunction "DA10P_53") (pintype "passive"))
    )
    (net (code "46") (name "/DB12_N") (class "Default")
      (node (ref "U16") (pin "54") (pinfunction "DA12M_54") (pintype "passive"))
    )
    (net (code "47") (name "/DB12_P") (class "Default")
      (node (ref "U16") (pin "55") (pinfunction "DA12P_55") (pintype "passive"))
    )
    (net (code "48") (name "/VCM_ADC") (class "Default")
      (node (ref "C190") (pin "2") (pinfunction "2_2") (pintype "passive"))
      (node (ref "C193") (pin "2") (pinfunction "2_2") (pintype "passive"))
      (node (ref "C203") (pin "2") (pinfunction "2_2") (pintype "passive"))
      (node (ref "C206") (pin "2") (pinfunction "2_2") (pintype "passive"))
      (node (ref "U16") (pin "23") (pinfunction "CM_23") (pintype "passive"))
      (node (ref "U17") (pin "11") (pinfunction "VOCM2_11") (pintype "passive"))
      (node (ref "U17") (pin "17") (pinfunction "VOCM1_17") (pintype "passive"))
    )
    (net (code "49") (name "1V8") (class "Default")
      (node (ref "C217") (pin "2") (pinfunction "2_2") (pintype "passive"))
      (node (ref "C218") (pin "2") (pinfunction "2_2") (pintype "passive"))
      (node (ref "C219") (pin "2") (pinfunction "2_2") (pintype "passive"))
      (node (ref "C220") (pin "2") (pinfunction "2_2") (pintype "passive"))
      (node (ref "C221") (pin "2") (pinfunction "2_2") (pintype "passive"))
      (node (ref "U16") (pin "1") (pinfunction "DRVDD_1") (pintype "passive"))
      (node (ref "U16") (pin "38") (pinfunction "DRVDD_38") (pintype "passive"))
      (node (ref "U16") (pin "48") (pinfunction "DRVDD_48") (pintype "passive"))
      (node (ref "U16") (pin "58") (pinfunction "DRVDD_58") (pintype "passive"))
    )
    (net (code "50") (name "3V3A") (class "Default")
      (node (ref "C212") (pin "2") (pinfunction "2_2") (pintype "passive"))
      (node (ref "C213") (pin "2") (pinfunction "2_2") (pintype "passive"))
      (node (ref "C214") (pin "2") (pinfunction "2_2") (pintype "passive"))
      (node (ref "C215") (pin "2") (pinfunction "2_2") (pintype "passive"))
      (node (ref "C216") (pin "2") (pinfunction "2_2") (pintype "passive"))
      (node (ref "U16") (pin "16") (pinfunction "AVDD_16") (pintype "passive"))
      (node (ref "U16") (pin "33") (pinfunction "AVDD_33") (pintype "passive"))
      (node (ref "U16") (pin "34") (pinfunction "AVDD_34") (pintype "passive"))
    )
    (net (code "51") (name "5V") (class "Default")
      (node (ref "C188") (pin "1") (pinfunction "1_1") (pintype "passive"))
      (node (ref "C189") (pin "2") (pinfunction "2_2") (pintype "passive"))
      (node (ref "C191") (pin "1") (pinfunction "1_1") (pintype "passive"))
      (node (ref "C192") (pin "2") (pinfunction "2_2") (pintype "passive"))
      (node (ref "C197") (pin "1") (pinfunction "1_1") (pintype "passive"))
      (node (ref "C201") (pin "1") (pinfunction "1_1") (pintype "passive"))
      (node (ref "C202") (pin "2") (pinfunction "2_2") (pintype "passive"))
      (node (ref "C204") (pin "1") (pinfunction "1_1") (pintype "passive"))
      (node (ref "C205") (pin "2") (pinfunction "2_2") (pintype "passive"))
      (node (ref "U17") (pin "10") (pinfunction "+VS2_10") (pintype "passive"))
      (node (ref "U17") (pin "14") (pinfunction "~{PD}2_14") (pintype "passive"))
      (node (ref "U17") (pin "20") (pinfunction "~{PD}1_20") (pintype "passive"))
      (node (ref "U17") (pin "3") (pinfunction "+VS1_3") (pintype "passive"))
      (node (ref "U17") (pin "4") (pinfunction "+VS1_4") (pintype "passive"))
      (node (ref "U17") (pin "9") (pinfunction "+VS2_9") (pintype "passive"))
    )
    (net (code "52") (name "GND") (class "Default")
      (node (ref "C188") (pin "2") (pinfunction "2_2") (pintype "passive"))
      (node (ref "C189") (pin "1") (pinfunction "1_1") (pintype "passive"))
      (node (ref "C190") (pin "1") (pinfunction "1_1") (pintype "passive"))
      (node (ref "C191") (pin "2") (pinfunction "2_2") (pintype "passive"))
      (node (ref "C192") (pin "1") (pinfunction "1_1") (pintype "passive"))
      (node (ref "C193") (pin "1") (pinfunction "1_1") (pintype "passive"))
      (node (ref "C195") (pin "1") (pinfunction "1_1") (pintype "passive"))
      (node (ref "C196") (pin "1") (pinfunction "1_1") (pintype "passive"))
      (node (ref "C197") (pin "2") (pinfunction "2_2") (pintype "passive"))
      (node (ref "C198") (pin "1") (pinfunction "1_1") (pintype "passive"))
      (node (ref "C201") (pin "2") (pinfunction "2_2") (pintype "passive"))
      (node (ref "C202") (pin "1") (pinfunction "1_1") (pintype "passive"))
      (node (ref "C203") (pin "1") (pinfunction "1_1") (pintype "passive"))
      (node (ref "C204") (pin "2") (pinfunction "2_2") (pintype "passive"))
      (node (ref "C205") (pin "1") (pinfunction "1_1") (pintype "passive"))
      (node (ref "C206") (pin "1") (pinfunction "1_1") (pintype "passive"))
      (node (ref "C208") (pin "1") (pinfunction "1_1") (pintype "passive"))
      (node (ref "C209") (pin "1") (pinfunction "1_1") (pintype "passive"))
      (node (ref "C212") (pin "1") (pinfunction "1_1") (pintype "passive"))
      (node (ref "C213") (pin "1") (pinfunction "1_1") (pintype "passive"))
      (node (ref "C214") (pin "1") (pinfunction "1_1") (pintype "passive"))
      (node (ref "C215") (pin "1") (pinfunction "1_1") (pintype "passive"))
      (node (ref "C216") (pin "1") (pinfunction "1_1") (pintype "passive"))
      (node (ref "C217") (pin "1") (pinfunction "1_1") (pintype "passive"))
      (node (ref "C218") (pin "1") (pinfunction "1_1") (pintype "passive"))
      (node (ref "C219") (pin "1") (pinfunction "1_1") (pintype "passive"))
      (node (ref "C220") (pin "1") (pinfunction "1_1") (pintype "passive"))
      (node (ref "C221") (pin "1") (pinfunction "1_1") (pintype "passive"))
      (node (ref "D8") (pin "2") (pinfunction "i/o_2") (pintype "passive"))
      (node (ref "D9") (pin "2") (pinfunction "i/o_2") (pintype "passive"))
      (node (ref "J4") (pin "2") (pinfunction "2_2") (pintype "passive"))
      (node (ref "J4") (pin "3") (pinfunction "3_3") (pintype "passive"))
      (node (ref "J4") (pin "4") (pinfunction "4_4") (pintype "passive"))
      (node (ref "J4") (pin "5") (pinfunction "5_5") (pintype "passive"))
      (node (ref "J5") (pin "2") (pinfunction "2_2") (pintype "passive"))
      (node (ref "J5") (pin "3") (pinfunction "3_3") (pintype "passive"))
      (node (ref "J5") (pin "4") (pinfunction "4_4") (pintype "passive"))
      (node (ref "J5") (pin "5") (pinfunction "5_5") (pintype "passive"))
      (node (ref "R118") (pin "1") (pinfunction "1_1") (pintype "passive"))
      (node (ref "R126") (pin "1") (pinfunction "1_1") (pintype "passive"))
      (node (ref "R60") (pin "1") (pinfunction "1_1") (pintype "passive"))
      (node (ref "R61") (pin "1") (pinfunction "1_1") (pintype "passive"))
      (node (ref "U16") (pin "17") (pinfunction "AGND_17") (pintype "passive"))
      (node (ref "U16") (pin "18") (pinfunction "AGND_18") (pintype "passive"))
      (node (ref "U16") (pin "21") (pinfunction "AGND_21") (pintype "passive"))
      (node (ref "U16") (pin "24") (pinfunction "AGND_24") (pintype "passive"))
      (node (ref "U16") (pin "27") (pinfunction "AGND_27") (pintype "passive"))
      (node (ref "U16") (pin "28") (pinfunction "AGND_28") (pintype "passive"))
      (node (ref "U16") (pin "31") (pinfunction "AGND_31") (pintype "passive"))
      (node (ref "U16") (pin "32") (pinfunction "AGND_32") (pintype "passive"))
      (node (ref "U16") (pin "39") (pinfunction "DRGND_39") (pintype "passive"))
      (node (ref "U16") (pin "49") (pinfunction "DRGND_49") (pintype "passive"))
      (node (ref "U16") (pin "59") (pinfunction "DRGND_59") (pintype "passive"))
      (node (ref "U16") (pin "PAD") (pinfunction "DRGND_PAD") (pintype "passive"))
    )
    (net (code "53") (name "Net-(C194-Pad1)") (class "Default")
      (node (ref "C194") (pin "1") (pinfunction "1_1") (pintype "passive"))
      (node (ref "L8") (pin "1") (pinfunction "1_1") (pintype "passive"))
      (node (ref "R117") (pin "1") (pinfunction "1_1") (pintype "passive"))
      (node (ref "R121") (pin "2") (pinfunction "2_2") (pintype "passive"))
    )
    (net (code "54") (name "Net-(C194-Pad2)") (class "Default")
      (node (ref "C194") (pin "2") (pinfunction "2_2") (pintype "passive"))
      (node (ref "L7") (pin "1") (pinfunction "1_1") (pintype "passive"))
      (node (ref "R116") (pin "2") (pinfunction "2_2") (pintype "passive"))
      (node (ref "R117") (pin "2") (pinfunction "2_2") (pintype "passive"))
    )
    (net (code "55") (name "Net-(C207-Pad1)") (class "Default")
      (node (ref "C207") (pin "1") (pinfunction "1_1") (pintype "passive"))
      (node (ref "L10") (pin "1") (pinfunction "1_1") (pintype "passive"))
      (node (ref "R125") (pin "1") (pinfunction "1_1") (pintype "passive"))
      (node (ref "R129") (pin "2") (pinfunction "2_2") (pintype "passive"))
    )
    (net (code "56") (name "Net-(C207-Pad2)") (class "Default")
      (node (ref "C207") (pin "2") (pinfunction "2_2") (pintype "passive"))
      (node (ref "L9") (pin "1") (pinfunction "1_1") (pintype "passive"))
      (node (ref "R124") (pin "2") (pinfunction "2_2") (pintype "passive"))
      (node (ref "R125") (pin "2") (pinfunction "2_2") (pintype "passive"))
    )
    (net (code "57") (name "Net-(D8-i{slash}o-Pad1)") (class "Default")
      (node (ref "D8") (pin "1") (pinfunction "i/o_1") (pintype "passive"))
      (node (ref "J4") (pin "1") (pinfunction "1_1") (pintype "passive"))
      (node (ref "R118") (pin "2") (pinfunction "2_2") (pintype "passive"))
      (node (ref "RG1") (pin "2") (pinfunction "2_2") (pintype "passive"))
    )
    (net (code "58") (name "Net-(D9-i{slash}o-Pad1)") (class "Default")
      (node (ref "D9") (pin "1") (pinfunction "i/o_1") (pintype "passive"))
      (node (ref "J5") (pin "1") (pinfunction "1_1") (pintype "passive"))
      (node (ref "R126") (pin "2") (pinfunction "2_2") (pintype "passive"))
      (node (ref "RG2") (pin "2") (pinfunction "2_2") (pintype "passive"))
    )
    (net (code "59") (name "Net-(L7-Pad2)") (class "Default")
      (node (ref "L7") (pin "2") (pinfunction "2_2") (pintype "passive"))
      (node (ref "R115") (pin "1") (pinfunction "1_1") (pintype "passive"))
    )
    (net (code "60") (name "Net-(L8-Pad2)") (class "Default")
      (node (ref "L8") (pin "2") (pinfunction "2_2") (pintype "passive"))
      (node (ref "R120") (pin "1") (pinfunction "1_1") (pintype "passive"))
    )
    (net (code "61") (name "Net-(L9-Pad2)") (class "Default")
      (node (ref "L9") (pin "2") (pinfunction "2_2") (pintype "passive"))
      (node (ref "R123") (pin "1") (pinfunction "1_1") (pintype "passive"))
    )
    (net (code "62") (name "Net-(L10-Pad2)") (class "Default")
      (node (ref "L10") (pin "2") (pinfunction "2_2") (pintype "passive"))
      (node (ref "R128") (pin "1") (pinfunction "1_1") (pintype "passive"))
    )
    (net (code "63") (name "Net-(R119-Pad2)") (class "Default")
      (node (ref "R119") (pin "2") (pinfunction "2_2") (pintype "passive"))
      (node (ref "R60") (pin "2") (pinfunction "2_2") (pintype "passive"))
    )
    (net (code "64") (name "Net-(R127-Pad2)") (class "Default")
      (node (ref "R127") (pin "2") (pinfunction "2_2") (pintype "passive"))
      (node (ref "R61") (pin "2") (pinfunction "2_2") (pintype "passive"))
    )
    (net (code "65") (name "Net-(U16A-INM_A)") (class "Default")
      (node (ref "R129") (pin "1") (pinfunction "1_1") (pintype "passive"))
      (node (ref "U16") (pin "30") (pinfunction "INM_A_30") (pintype "passive"))
    )
    (net (code "66") (name "Net-(U16A-INP_A)") (class "Default")
      (node (ref "R124") (pin "1") (pinfunction "1_1") (pintype "passive"))
      (node (ref "U16") (pin "29") (pinfunction "INP_A_29") (pintype "passive"))
    )
    (net (code "67") (name "Net-(U16B-INM_B)") (class "Default")
      (node (ref "R121") (pin "1") (pinfunction "1_1") (pintype "passive"))
      (node (ref "U16") (pin "20") (pinfunction "INM_B_20") (pintype "passive"))
    )
    (net (code "68") (name "Net-(U16B-INP_B)") (class "Default")
      (node (ref "R116") (pin "1") (pinfunction "1_1") (pintype "passive"))
      (node (ref "U16") (pin "19") (pinfunction "INP_B_19") (pintype "passive"))
    )
    (net (code "69") (name "Net-(U16C-SDOUT)") (class "Default")
      (node (ref "R132") (pin "2") (pinfunction "2_2") (pintype "passive"))
      (node (ref "U16") (pin "64") (pinfunction "SDOUT_64") (pintype "passive"))
    )
    (net (code "70") (name "Net-(U17A-+FB1)") (class "Default")
      (node (ref "R122") (pin "1") (pinfunction "1_1") (pintype "passive"))
      (node (ref "U17") (pin "2") (pinfunction "+FB1_2") (pintype "passive"))
    )
    (net (code "71") (name "Net-(U17A-+IN1)") (class "Default")
      (node (ref "RF1") (pin "2") (pinfunction "2_2") (pintype "passive"))
      (node (ref "RG1") (pin "1") (pinfunction "1_1") (pintype "passive"))
      (node (ref "U17") (pin "24") (pinfunction "+IN1_24") (pintype "passive"))
    )
    (net (code "72") (name "Net-(U17A--FB1)") (class "Default")
      (node (ref "RF1") (pin "1") (pinfunction "1_1") (pintype "passive"))
      (node (ref "U17") (pin "23") (pinfunction "-FB1_23") (pintype "passive"))
    )
    (net (code "73") (name "Net-(U17A--IN1)") (class "Default")
      (node (ref "R119") (pin "1") (pinfunction "1_1") (pintype "passive"))
      (node (ref "R122") (pin "2") (pinfunction "2_2") (pintype "passive"))
      (node (ref "U17") (pin "1") (pinfunction "-IN1_1") (pintype "passive"))
    )
    (net (code "74") (name "Net-(U17B-+FB2)") (class "Default")
      (node (ref "R130") (pin "1") (pinfunction "1_1") (pintype "passive"))
      (node (ref "U17") (pin "8") (pinfunction "+FB2_8") (pintype "passive"))
    )
    (net (code "75") (name "Net-(U17B-+IN2)") (class "Default")
      (node (ref "RF2") (pin "2") (pinfunction "2_2") (pintype "passive"))
      (node (ref "RG2") (pin "1") (pinfunction "1_1") (pintype "passive"))
      (node (ref "U17") (pin "6") (pinfunction "+IN2_6") (pintype "passive"))
    )
    (net (code "76") (name "Net-(U17B--FB2)") (class "Default")
      (node (ref "RF2") (pin "1") (pinfunction "1_1") (pintype "passive"))
      (node (ref "U17") (pin "5") (pinfunction "-FB2_5") (pintype "passive"))
    )
    (net (code "77") (name "Net-(U17B--IN2)") (class "Default")
      (node (ref "R127") (pin "1") (pinfunction "1_1") (pintype "passive"))
      (node (ref "R130") (pin "2") (pinfunction "2_2") (pintype "passive"))
      (node (ref "U17") (pin "7") (pinfunction "-IN2_7") (pintype "passive"))
    )
    (net (code "78") (name "unconnected-(U16C-NC-Pad22)") (class "Default")
      (node (ref "U16") (pin "22") (pinfunction "NC_22") (pintype "passive+no_connect"))
    )
  )
)
